# Voltage_Indicator.net
KiCad netlist of a schematic drawn in Altium Designer
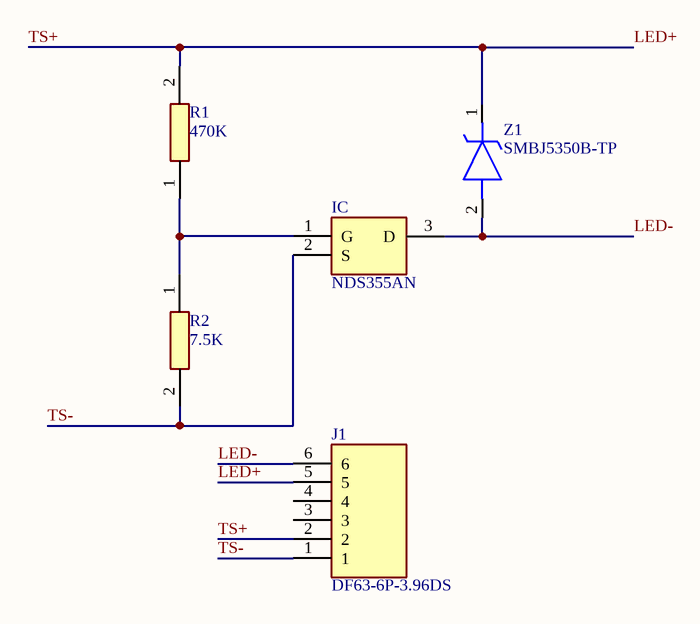
[diagram p0: Voltage Indicator.SchDoc]

(export (version "E")
  (design (tool "Eeschema 10.0.6"))
  (components
    (comp (ref "IC")
      (value "NDS355AN")
      (footprint "SamacSys:SOT95P251X112-3N")
      (description "Integrated Circuit")
      (fields (field (name "MOUSER PART NUMBER") "512-NDS355AN"))
      (libsource (lib "*") (part "NDS355AN"))
    )
    (comp (ref "J1")
      (value "DF63-6P-3.96DS")
      (footprint "SamacSys:DF636P396DS")
      (description "Connector")
      (fields (field (name "MOUSER PART NUMBER") "798-DF63-6P-3.96DS"))
      (libsource (lib "*") (part "DF63-6P-3.96DS"))
    )
    (comp (ref "R1")
      (value "470K")
      (footprint "SamacSys:RESAD1800W63L800D250")
      (description "Resistor")
      (fields
        (field (name "MANUFACTURER_PART_NUMBER") "PR01000104700JR500")
        (field (name "MOUSER PART NUMBER") "594-5073NW470R0J")
      )
      (libsource (lib "*") (part "PR01000104700JR500"))
    )
    (comp (ref "R2")
      (value "7.5K")
      (footprint "SamacSys:RESAD1800W63L800D250")
      (description "Resistor")
      (fields
        (field (name "MANUFACTURER_PART_NUMBER") "PR01000104700JR500")
        (field (name "MOUSER PART NUMBER") "594-5073NW470R0J")
      )
      (libsource (lib "") (part "PR01000104700JR500_1"))
    )
    (comp (ref "Z1")
      (value "SMBJ5350B-TP")
      (footprint "SamacSys:DIOM5336X261N")
      (description "Zener Diode")
      (fields (field (name "MOUSER PART NUMBER") "833-SMBJ5350B-TP"))
      (libsource (lib "*") (part "SMBJ5350B-TP"))
    )
  )
  (nets
    (net (code "1") (name "/LED+") (class "Default")
      (node (ref "J1") (pin "2") (pinfunction "2_2") (pintype "passive"))
      (node (ref "J1") (pin "5") (pinfunction "5_5") (pintype "passive"))
      (node (ref "R1") (pin "2") (pinfunction "2_2") (pintype "passive"))
      (node (ref "Z1") (pin "1") (pinfunction "K_1") (pintype "passive"))
    )
    (net (code "2") (name "/LED-") (class "Default")
      (node (ref "IC") (pin "3") (pinfunction "D_3") (pintype "passive"))
      (node (ref "J1") (pin "6") (pinfunction "6_6") (pintype "passive"))
      (node (ref "Z1") (pin "2") (pinfunction "A_2") (pintype "passive"))
    )
    (net (code "3") (name "/TS-") (class "Default")
      (node (ref "IC") (pin "2") (pinfunction "S_2") (pintype "passive"))
      (node (ref "J1") (pin "1") (pinfunction "1_1") (pintype "passive"))
      (node (ref "R2") (pin "2") (pinfunction "2_2") (pintype "passive"))
    )
    (net (code "4") (name "Net-(IC-G)") (class "Default")
      (node (ref "IC") (pin "1") (pinfunction "G_1") (pintype "passive"))
      (node (ref "R1") (pin "1") (pinfunction "1_1") (pintype "passive"))
      (node (ref "R2") (pin "1") (pinfunction "1_1") (pintype "passive"))
    )
    (net (code "5") (name "unconnected-(J1-Pad3)") (class "Default")
      (node (ref "J1") (pin "3") (pinfunction "3_3") (pintype "passive"))
    )
    (net (code "6") (name "unconnected-(J1-Pad4)") (class "Default")
      (node (ref "J1") (pin "4") (pinfunction "4_4") (pintype "passive"))
    )
  )
)
